# Main.net
KiCad netlist of a schematic drawn in EAGLE
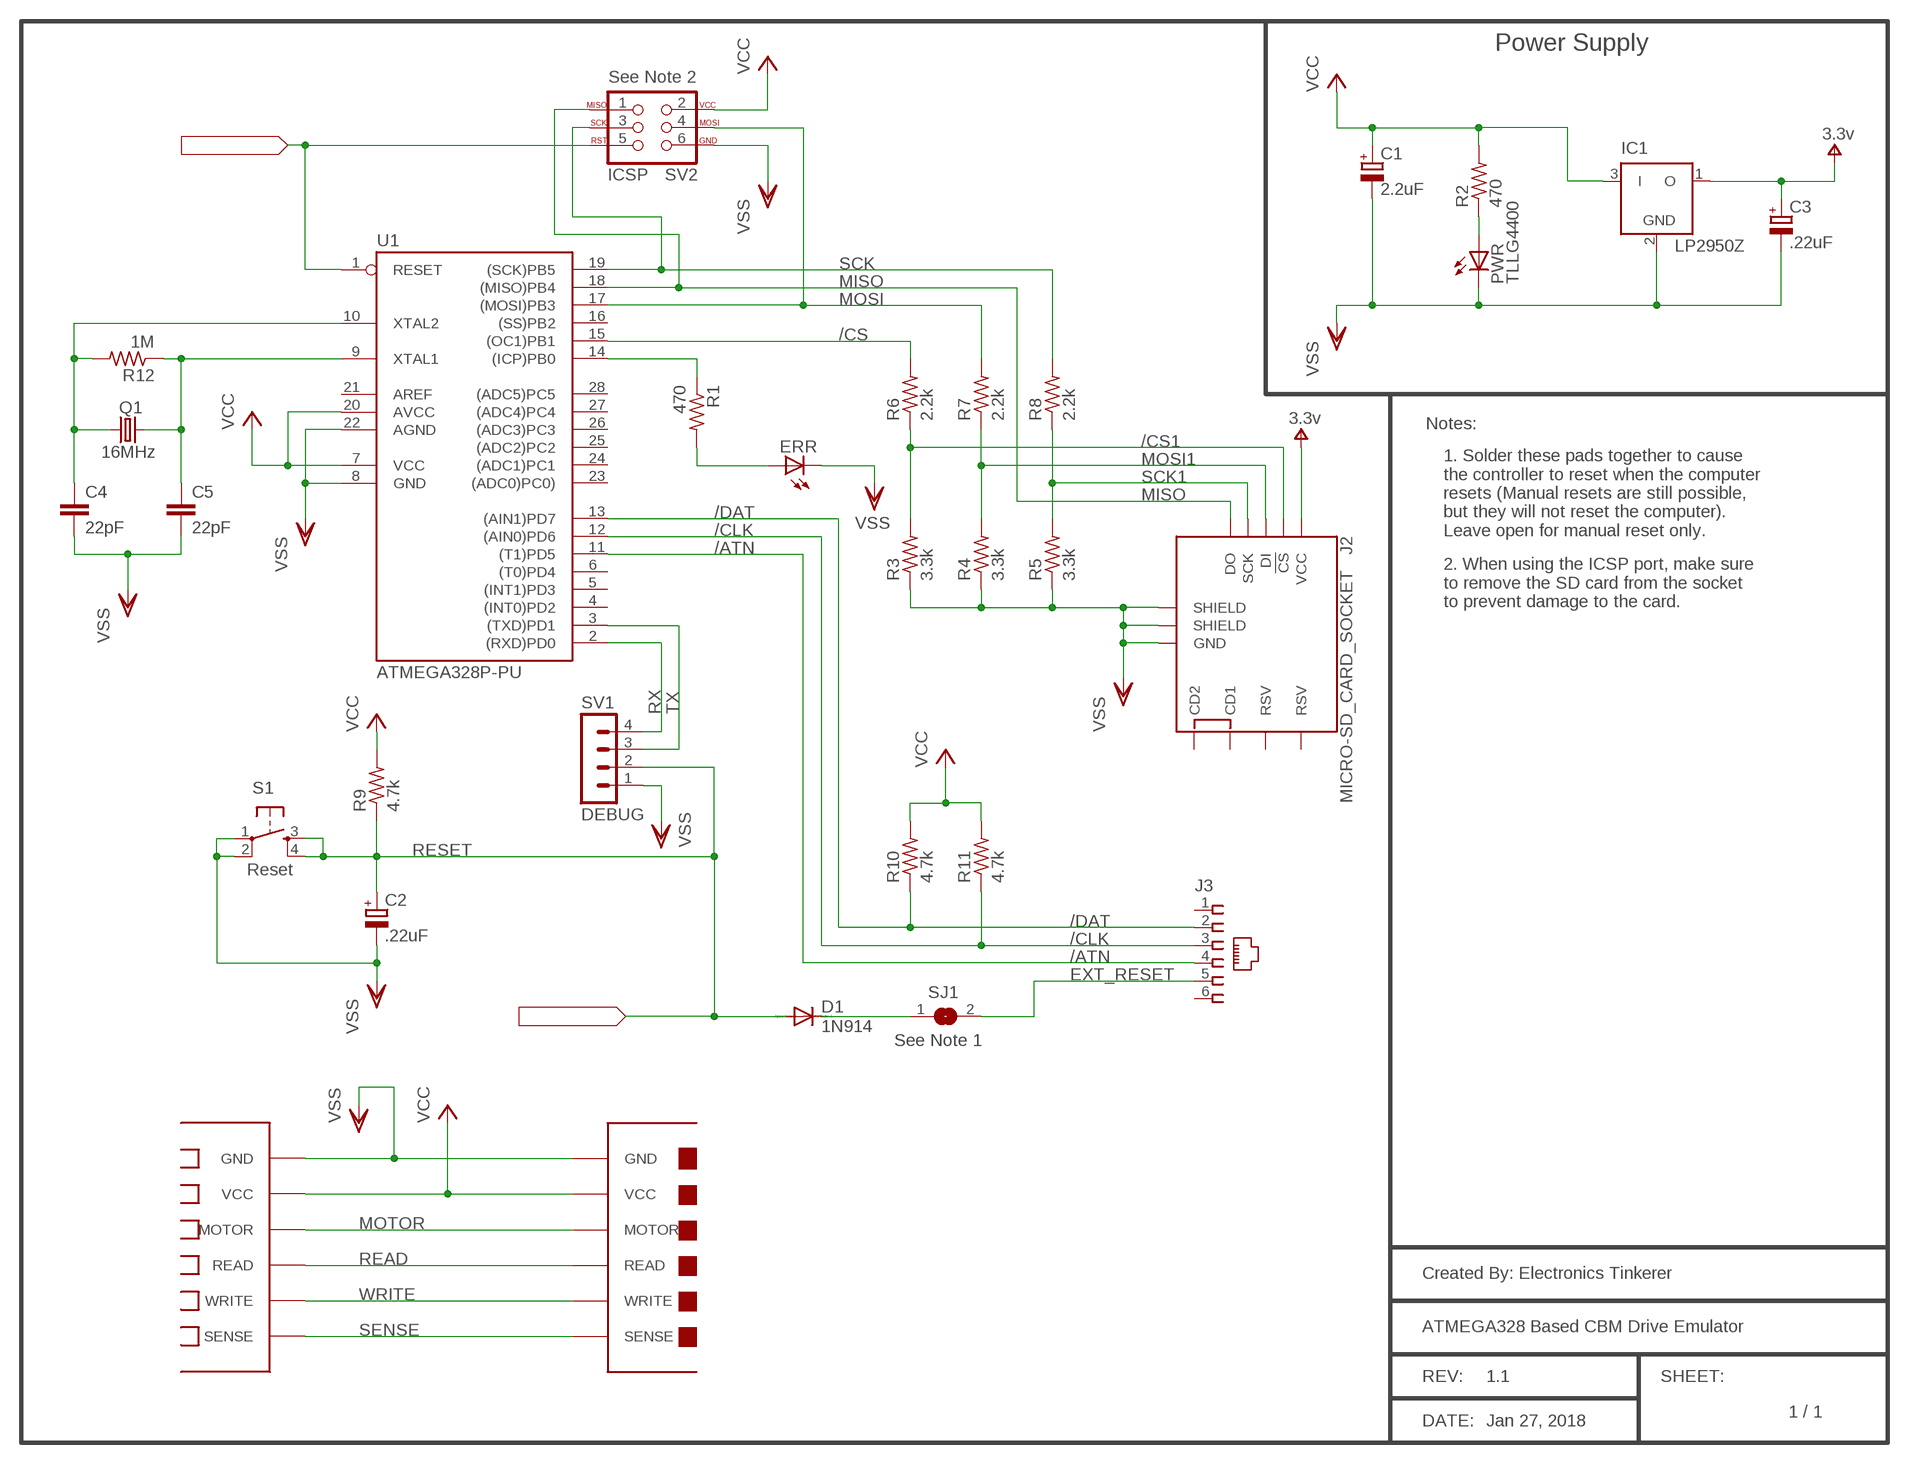
[diagram p0: schematic, sheet 1]

(export (version "E")
  (design (tool "Eeschema 10.0.6"))
  (components
    (comp (ref "C1")
      (value "2.2uF")
      (footprint "eagle-import:E2-5")
      (libsource (lib "eagle-import") (part "CPOL-EUE2-5"))
    )
    (comp (ref "C2")
      (value ".22uF")
      (footprint "eagle-import:E1,5-4")
      (libsource (lib "eagle-import") (part "CPOL-EU"))
    )
    (comp (ref "C3")
      (value ".22uF")
      (footprint "eagle-import:E1,5-4")
      (libsource (lib "eagle-import") (part "CPOL-EU"))
    )
    (comp (ref "C4")
      (value "22pF")
      (footprint "eagle-import:C050-024X044")
      (libsource (lib "eagle-import") (part "C-EU050-024X044"))
    )
    (comp (ref "C5")
      (value "22pF")
      (footprint "eagle-import:C050-024X044")
      (libsource (lib "eagle-import") (part "C-EU050-024X044"))
    )
    (comp (ref "D1")
      (value "1N914")
      (footprint "eagle-import:DO41-5")
      (libsource (lib "eagle-import") (part "1N914"))
    )
    (comp (ref "ERR")
      (value "TLLR4400")
      (footprint "eagle-import:LED3MM")
      (fields (field (name "MF") "VISHAY SEMICONDUCTOR"))
      (libsource (lib "eagle-import") (part "TLLR4400"))
    )
    (comp (ref "IC1")
      (value "LP2950Z")
      (footprint "eagle-import:TO92")
      (libsource (lib "eagle-import") (part "LP2950Z"))
    )
    (comp (ref "J2")
      (value "MICRO-SD_CARD_SOCKET")
      (footprint "eagle-import:MICRO-SD-SOCKET")
      (libsource (lib "eagle-import") (part "MICRO-SD_CARD_SOCKET"))
    )
    (comp (ref "J3")
      (value "520470-3")
      (footprint "eagle-import:520470-3")
      (libsource (lib "eagle-import") (part "520470-3"))
    )
    (comp (ref "PWR")
      (value "TLLG4400")
      (footprint "eagle-import:LED3MM")
      (fields (field (name "MF") "VISHAY SEMICONDUCTOR"))
      (libsource (lib "eagle-import") (part "TLLG4400"))
    )
    (comp (ref "Q1")
      (value "16MHz")
      (footprint "eagle-import:HC49_S")
      (libsource (lib "eagle-import") (part "CRYSTALHC49S"))
    )
    (comp (ref "R1")
      (value "470")
      (footprint "eagle-import:0204_5")
      (libsource (lib "eagle-import") (part "R-US_0204/5"))
    )
    (comp (ref "R2")
      (value "470")
      (footprint "eagle-import:0204_5")
      (libsource (lib "eagle-import") (part "R-US_0204/5"))
    )
    (comp (ref "R3")
      (value "3.3k")
      (footprint "eagle-import:0204_5")
      (libsource (lib "eagle-import") (part "R-US_0204/5"))
    )
    (comp (ref "R4")
      (value "3.3k")
      (footprint "eagle-import:0204_5")
      (libsource (lib "eagle-import") (part "R-US_0204/5"))
    )
    (comp (ref "R5")
      (value "3.3k")
      (footprint "eagle-import:0204_5")
      (libsource (lib "eagle-import") (part "R-US_0204/5"))
    )
    (comp (ref "R6")
      (value "2.2k")
      (footprint "eagle-import:0204_5")
      (libsource (lib "eagle-import") (part "R-US_0204/5"))
    )
    (comp (ref "R7")
      (value "2.2k")
      (footprint "eagle-import:0204_5")
      (libsource (lib "eagle-import") (part "R-US_0204/5"))
    )
    (comp (ref "R8")
      (value "2.2k")
      (footprint "eagle-import:0204_5")
      (libsource (lib "eagle-import") (part "R-US_0204/5"))
    )
    (comp (ref "R9")
      (value "4.7k")
      (footprint "eagle-import:0204_5")
      (libsource (lib "eagle-import") (part "R-US_0204/5"))
    )
    (comp (ref "R10")
      (value "4.7k")
      (footprint "eagle-import:0204_5")
      (libsource (lib "eagle-import") (part "R-US_0204/5"))
    )
    (comp (ref "R11")
      (value "4.7k")
      (footprint "eagle-import:0204_5")
      (libsource (lib "eagle-import") (part "R-US_0204/5"))
    )
    (comp (ref "R12")
      (value "1M")
      (footprint "eagle-import:0204_5")
      (libsource (lib "eagle-import") (part "R-US_0204/5"))
    )
    (comp (ref "S1")
      (value "DTS-6")
      (footprint "eagle-import:DTS-6")
      (fields (field (name "DESIGNATOR") "Reset"))
      (libsource (lib "eagle-import") (part "DTS-6"))
    )
    (comp (ref "SJ1") (value "SJ") (footprint "eagle-import:SJ") (libsource (lib "eagle-import") (part "SJ")))
    (comp (ref "SV1")
      (value "DEBUG")
      (footprint "eagle-import:MA04-1")
      (libsource (lib "eagle-import") (part "MA04-1"))
    )
    (comp (ref "SV2")
      (value "AVR_SPI_PROG")
      (footprint "eagle-import:2X3")
      (fields (field (name "TYPE") "ICSP"))
      (libsource (lib "eagle-import") (part "AVR_SPI_PROG_3X2PTH"))
    )
    (comp (ref "U$1")
      (value "CASSETT-BOARDCEC-6")
      (footprint "eagle-import:SOLDER-PADS_3,96-M")
      (libsource (lib "eagle-import") (part "CASSETT-BOARDCEC-6"))
    )
    (comp (ref "U$2")
      (value "CASSETT-CON")
      (footprint "eagle-import:SOLDER-PADS_3,96-F")
      (libsource (lib "eagle-import") (part "CASSETT-CON"))
    )
    (comp (ref "U1")
      (value "ATMEGA328P-PU")
      (footprint "eagle-import:DIL28-3")
      (libsource (lib "eagle-import") (part "ATMEGA328P-PU"))
    )
  )
  (nets
    (net (code "1") (name "/EXT_RESET") (class "Default")
      (node (ref "J3") (pin "5") (pinfunction "5_5") (pintype "passive"))
      (node (ref "SJ1") (pin "2") (pinfunction "2_2") (pintype "passive"))
    )
    (net (code "2") (name "/MISO") (class "Default")
      (node (ref "J2") (pin "DO") (pinfunction "DO_DO") (pintype "bidirectional"))
      (node (ref "SV2") (pin "1") (pinfunction "1_1") (pintype "passive"))
      (node (ref "U1") (pin "18") (pinfunction "(MISO)PB4_18") (pintype "bidirectional"))
    )
    (net (code "3") (name "/MOSI") (class "Default")
      (node (ref "R7") (pin "2") (pinfunction "2_2") (pintype "passive"))
      (node (ref "SV2") (pin "4") (pinfunction "4_4") (pintype "passive"))
      (node (ref "U1") (pin "17") (pinfunction "(MOSI)PB3_17") (pintype "bidirectional"))
    )
    (net (code "4") (name "/MOSI1") (class "Default")
      (node (ref "J2") (pin "DI") (pinfunction "DI_DI") (pintype "bidirectional"))
      (node (ref "R4") (pin "2") (pinfunction "2_2") (pintype "passive"))
      (node (ref "R7") (pin "1") (pinfunction "1_1") (pintype "passive"))
    )
    (net (code "5") (name "/MOTOR") (class "Default")
      (node (ref "U$1") (pin "MOTOR") (pinfunction "MOTOR_MOTOR") (pintype "output"))
      (node (ref "U$2") (pin "MOTOR") (pinfunction "MOTOR_MOTOR") (pintype "output"))
    )
    (net (code "6") (name "/READ") (class "Default")
      (node (ref "U$1") (pin "READ") (pinfunction "READ_READ") (pintype "input"))
      (node (ref "U$2") (pin "READ") (pinfunction "READ_READ") (pintype "input"))
    )
    (net (code "7") (name "/RESET") (class "Default")
      (node (ref "C2") (pin "+") (pinfunction "+_+") (pintype "passive"))
      (node (ref "D1") (pin "A") (pinfunction "A_A") (pintype "passive"))
      (node (ref "R9") (pin "1") (pinfunction "1_1") (pintype "passive"))
      (node (ref "S1") (pin "3") (pinfunction "3_3") (pintype "passive"))
      (node (ref "S1") (pin "4") (pinfunction "4_4") (pintype "passive"))
      (node (ref "SV1") (pin "2") (pinfunction "2_2") (pintype "passive"))
      (node (ref "SV2") (pin "5") (pinfunction "5_5") (pintype "passive"))
      (node (ref "U1") (pin "1") (pinfunction "RESET_1") (pintype "input"))
    )
    (net (code "8") (name "/RX") (class "Default")
      (node (ref "SV1") (pin "4") (pinfunction "4_4") (pintype "passive"))
      (node (ref "U1") (pin "2") (pinfunction "(RXD)PD0_2") (pintype "bidirectional"))
    )
    (net (code "9") (name "/SCK") (class "Default")
      (node (ref "R8") (pin "2") (pinfunction "2_2") (pintype "passive"))
      (node (ref "SV2") (pin "3") (pinfunction "3_3") (pintype "passive"))
      (node (ref "U1") (pin "19") (pinfunction "(SCK)PB5_19") (pintype "bidirectional"))
    )
    (net (code "10") (name "/SCK1") (class "Default")
      (node (ref "J2") (pin "SCLK") (pinfunction "SCK_SCLK") (pintype "bidirectional"))
      (node (ref "R5") (pin "2") (pinfunction "2_2") (pintype "passive"))
      (node (ref "R8") (pin "1") (pinfunction "1_1") (pintype "passive"))
    )
    (net (code "11") (name "/SENSE") (class "Default")
      (node (ref "U$1") (pin "SENSE") (pinfunction "SENSE_SENSE") (pintype "input"))
      (node (ref "U$2") (pin "SENSE") (pinfunction "SENSE_SENSE") (pintype "input"))
    )
    (net (code "12") (name "/TX") (class "Default")
      (node (ref "SV1") (pin "3") (pinfunction "3_3") (pintype "passive"))
      (node (ref "U1") (pin "3") (pinfunction "(TXD)PD1_3") (pintype "bidirectional"))
    )
    (net (code "13") (name "/WRITE") (class "Default")
      (node (ref "U$1") (pin "WRITE") (pinfunction "WRITE_WRITE") (pintype "output"))
      (node (ref "U$2") (pin "WRITE") (pinfunction "WRITE_WRITE") (pintype "output"))
    )
    (net (code "14") (name "/{slash}ATN") (class "Default")
      (node (ref "J3") (pin "4") (pinfunction "4_4") (pintype "passive"))
      (node (ref "U1") (pin "11") (pinfunction "(T1)PD5_11") (pintype "bidirectional"))
    )
    (net (code "15") (name "/{slash}CLK") (class "Default")
      (node (ref "J3") (pin "3") (pinfunction "3_3") (pintype "passive"))
      (node (ref "R11") (pin "1") (pinfunction "1_1") (pintype "passive"))
      (node (ref "U1") (pin "12") (pinfunction "(AIN0)PD6_12") (pintype "bidirectional"))
    )
    (net (code "16") (name "/{slash}CS") (class "Default")
      (node (ref "R6") (pin "2") (pinfunction "2_2") (pintype "passive"))
      (node (ref "U1") (pin "15") (pinfunction "(OC1)PB1_15") (pintype "bidirectional"))
    )
    (net (code "17") (name "/{slash}CS1") (class "Default")
      (node (ref "J2") (pin "CS") (pinfunction "~{CS}_CS") (pintype "bidirectional"))
      (node (ref "R3") (pin "2") (pinfunction "2_2") (pintype "passive"))
      (node (ref "R6") (pin "1") (pinfunction "1_1") (pintype "passive"))
    )
    (net (code "18") (name "/{slash}DAT") (class "Default")
      (node (ref "J3") (pin "2") (pinfunction "2_2") (pintype "passive"))
      (node (ref "R10") (pin "1") (pinfunction "1_1") (pintype "passive"))
      (node (ref "U1") (pin "13") (pinfunction "(AIN1)PD7_13") (pintype "bidirectional"))
    )
    (net (code "19") (name "Net-(D1-PadC)") (class "Default")
      (node (ref "D1") (pin "C") (pinfunction "C_C") (pintype "passive"))
      (node (ref "SJ1") (pin "1") (pinfunction "1_1") (pintype "passive"))
    )
    (net (code "20") (name "Net-(ERR-PadA)") (class "Default")
      (node (ref "ERR") (pin "A") (pinfunction "A_A") (pintype "passive"))
      (node (ref "R1") (pin "2") (pinfunction "2_2") (pintype "passive"))
    )
    (net (code "21") (name "Net-(PWR-PadA)") (class "Default")
      (node (ref "PWR") (pin "A") (pinfunction "A_A") (pintype "passive"))
      (node (ref "R2") (pin "1") (pinfunction "1_1") (pintype "passive"))
    )
    (net (code "22") (name "Net-(U1-(ICP)PB0)") (class "Default")
      (node (ref "R1") (pin "1") (pinfunction "1_1") (pintype "passive"))
      (node (ref "U1") (pin "14") (pinfunction "(ICP)PB0_14") (pintype "bidirectional"))
    )
    (net (code "23") (name "Net-(U1-XTAL1)") (class "Default")
      (node (ref "C5") (pin "1") (pinfunction "1_1") (pintype "passive"))
      (node (ref "Q1") (pin "2") (pinfunction "2_2") (pintype "passive"))
      (node (ref "R12") (pin "1") (pinfunction "1_1") (pintype "passive"))
      (node (ref "U1") (pin "9") (pinfunction "XTAL1_9") (pintype "bidirectional"))
    )
    (net (code "24") (name "Net-(U1-XTAL2)") (class "Default")
      (node (ref "C4") (pin "1") (pinfunction "1_1") (pintype "passive"))
      (node (ref "Q1") (pin "1") (pinfunction "1_1") (pintype "passive"))
      (node (ref "R12") (pin "2") (pinfunction "2_2") (pintype "passive"))
      (node (ref "U1") (pin "10") (pinfunction "XTAL2_10") (pintype "bidirectional"))
    )
    (net (code "25") (name "V+") (class "Default")
      (node (ref "C3") (pin "+") (pinfunction "+_+") (pintype "passive"))
      (node (ref "IC1") (pin "1") (pinfunction "O_1") (pintype "input"))
      (node (ref "J2") (pin "VCC") (pinfunction "VCC_VCC") (pintype "bidirectional"))
    )
    (net (code "26") (name "VCC") (class "Default")
      (node (ref "C1") (pin "+") (pinfunction "+_+") (pintype "passive"))
      (node (ref "IC1") (pin "3") (pinfunction "I_3") (pintype "input"))
      (node (ref "R10") (pin "2") (pinfunction "2_2") (pintype "passive"))
      (node (ref "R11") (pin "2") (pinfunction "2_2") (pintype "passive"))
      (node (ref "R2") (pin "2") (pinfunction "2_2") (pintype "passive"))
      (node (ref "R9") (pin "2") (pinfunction "2_2") (pintype "passive"))
      (node (ref "SV2") (pin "2") (pinfunction "2_2") (pintype "passive"))
      (node (ref "U$1") (pin "VCC") (pinfunction "VCC_VCC") (pintype "power_in"))
      (node (ref "U$2") (pin "VCC") (pinfunction "VCC_VCC") (pintype "power_in"))
      (node (ref "U1") (pin "20") (pinfunction "AVCC_20") (pintype "power_in"))
      (node (ref "U1") (pin "7") (pinfunction "VCC_7") (pintype "power_in"))
    )
    (net (code "27") (name "VSS") (class "Default")
      (node (ref "C1") (pin "-") (pinfunction "-_-") (pintype "passive"))
      (node (ref "C2") (pin "-") (pinfunction "-_-") (pintype "passive"))
      (node (ref "C3") (pin "-") (pinfunction "-_-") (pintype "passive"))
      (node (ref "C4") (pin "2") (pinfunction "2_2") (pintype "passive"))
      (node (ref "C5") (pin "2") (pinfunction "2_2") (pintype "passive"))
      (node (ref "ERR") (pin "K") (pinfunction "C_K") (pintype "passive"))
      (node (ref "IC1") (pin "2") (pinfunction "GND_2") (pintype "power_in"))
      (node (ref "J2") (pin "GND") (pinfunction "GND_GND") (pintype "bidirectional"))
      (node (ref "J2") (pin "GND1") (pinfunction "SHIELD_GND1") (pintype "bidirectional"))
      (node (ref "J2") (pin "GND3") (pinfunction "SHIELD_GND3") (pintype "bidirectional"))
      (node (ref "PWR") (pin "K") (pinfunction "C_K") (pintype "passive"))
      (node (ref "R3") (pin "1") (pinfunction "1_1") (pintype "passive"))
      (node (ref "R4") (pin "1") (pinfunction "1_1") (pintype "passive"))
      (node (ref "R5") (pin "1") (pinfunction "1_1") (pintype "passive"))
      (node (ref "S1") (pin "1") (pinfunction "1_1") (pintype "passive"))
      (node (ref "S1") (pin "2") (pinfunction "2_2") (pintype "passive"))
      (node (ref "SV1") (pin "1") (pinfunction "1_1") (pintype "passive"))
      (node (ref "SV2") (pin "6") (pinfunction "6_6") (pintype "passive"))
      (node (ref "U$1") (pin "GND") (pinfunction "GND_GND") (pintype "power_in"))
      (node (ref "U$2") (pin "GND") (pinfunction "GND_GND") (pintype "power_in"))
      (node (ref "U1") (pin "22") (pinfunction "AGND_22") (pintype "power_in"))
      (node (ref "U1") (pin "8") (pinfunction "GND_8") (pintype "power_in"))
    )
    (net (code "28") (name "unconnected-(J2-PadCD1)") (class "Default")
      (node (ref "J2") (pin "CD1") (pinfunction "CD1_CD1") (pintype "bidirectional"))
    )
    (net (code "29") (name "unconnected-(J2-PadCD2)") (class "Default")
      (node (ref "J2") (pin "CD2") (pinfunction "CD2_CD2") (pintype "bidirectional"))
    )
    (net (code "30") (name "unconnected-(J2-RSV-PadRSV1)") (class "Default")
      (node (ref "J2") (pin "RSV1") (pinfunction "RSV_RSV1") (pintype "bidirectional"))
    )
    (net (code "31") (name "unconnected-(J2-RSV-PadRSV2)") (class "Default")
      (node (ref "J2") (pin "RSV2") (pinfunction "RSV_RSV2") (pintype "bidirectional"))
    )
    (net (code "32") (name "unconnected-(J3-Pad1)") (class "Default")
      (node (ref "J3") (pin "1") (pinfunction "1_1") (pintype "passive"))
    )
    (net (code "33") (name "unconnected-(J3-Pad6)") (class "Default")
      (node (ref "J3") (pin "6") (pinfunction "6_6") (pintype "passive"))
    )
    (net (code "34") (name "unconnected-(U1-(ADC0)PC0)-Pad23)") (class "Default")
      (node (ref "U1") (pin "23") (pinfunction "(ADC0)PC0)_23") (pintype "bidirectional"))
    )
    (net (code "35") (name "unconnected-(U1-(ADC1)PC1-Pad24)") (class "Default")
      (node (ref "U1") (pin "24") (pinfunction "(ADC1)PC1_24") (pintype "bidirectional"))
    )
    (net (code "36") (name "unconnected-(U1-(ADC2)PC2-Pad25)") (class "Default")
      (node (ref "U1") (pin "25") (pinfunction "(ADC2)PC2_25") (pintype "bidirectional"))
    )
    (net (code "37") (name "unconnected-(U1-(ADC3)PC3-Pad26)") (class "Default")
      (node (ref "U1") (pin "26") (pinfunction "(ADC3)PC3_26") (pintype "bidirectional"))
    )
    (net (code "38") (name "unconnected-(U1-(ADC4)PC4-Pad27)") (class "Default")
      (node (ref "U1") (pin "27") (pinfunction "(ADC4)PC4_27") (pintype "bidirectional"))
    )
    (net (code "39") (name "unconnected-(U1-(ADC5)PC5-Pad28)") (class "Default")
      (node (ref "U1") (pin "28") (pinfunction "(ADC5)PC5_28") (pintype "bidirectional"))
    )
    (net (code "40") (name "unconnected-(U1-(INT0)PD2-Pad4)") (class "Default")
      (node (ref "U1") (pin "4") (pinfunction "(INT0)PD2_4") (pintype "bidirectional"))
    )
    (net (code "41") (name "unconnected-(U1-(INT1)PD3-Pad5)") (class "Default")
      (node (ref "U1") (pin "5") (pinfunction "(INT1)PD3_5") (pintype "bidirectional"))
    )
    (net (code "42") (name "unconnected-(U1-(SS)PB2-Pad16)") (class "Default")
      (node (ref "U1") (pin "16") (pinfunction "(SS)PB2_16") (pintype "bidirectional"))
    )
    (net (code "43") (name "unconnected-(U1-(T0)PD4-Pad6)") (class "Default")
      (node (ref "U1") (pin "6") (pinfunction "(T0)PD4_6") (pintype "bidirectional"))
    )
    (net (code "44") (name "unconnected-(U1-AREF-Pad21)") (class "Default")
      (node (ref "U1") (pin "21") (pinfunction "AREF_21") (pintype "passive"))
    )
  )
)
